# 40bus-nano32.net
KiCad netlist of a schematic drawn in EAGLE
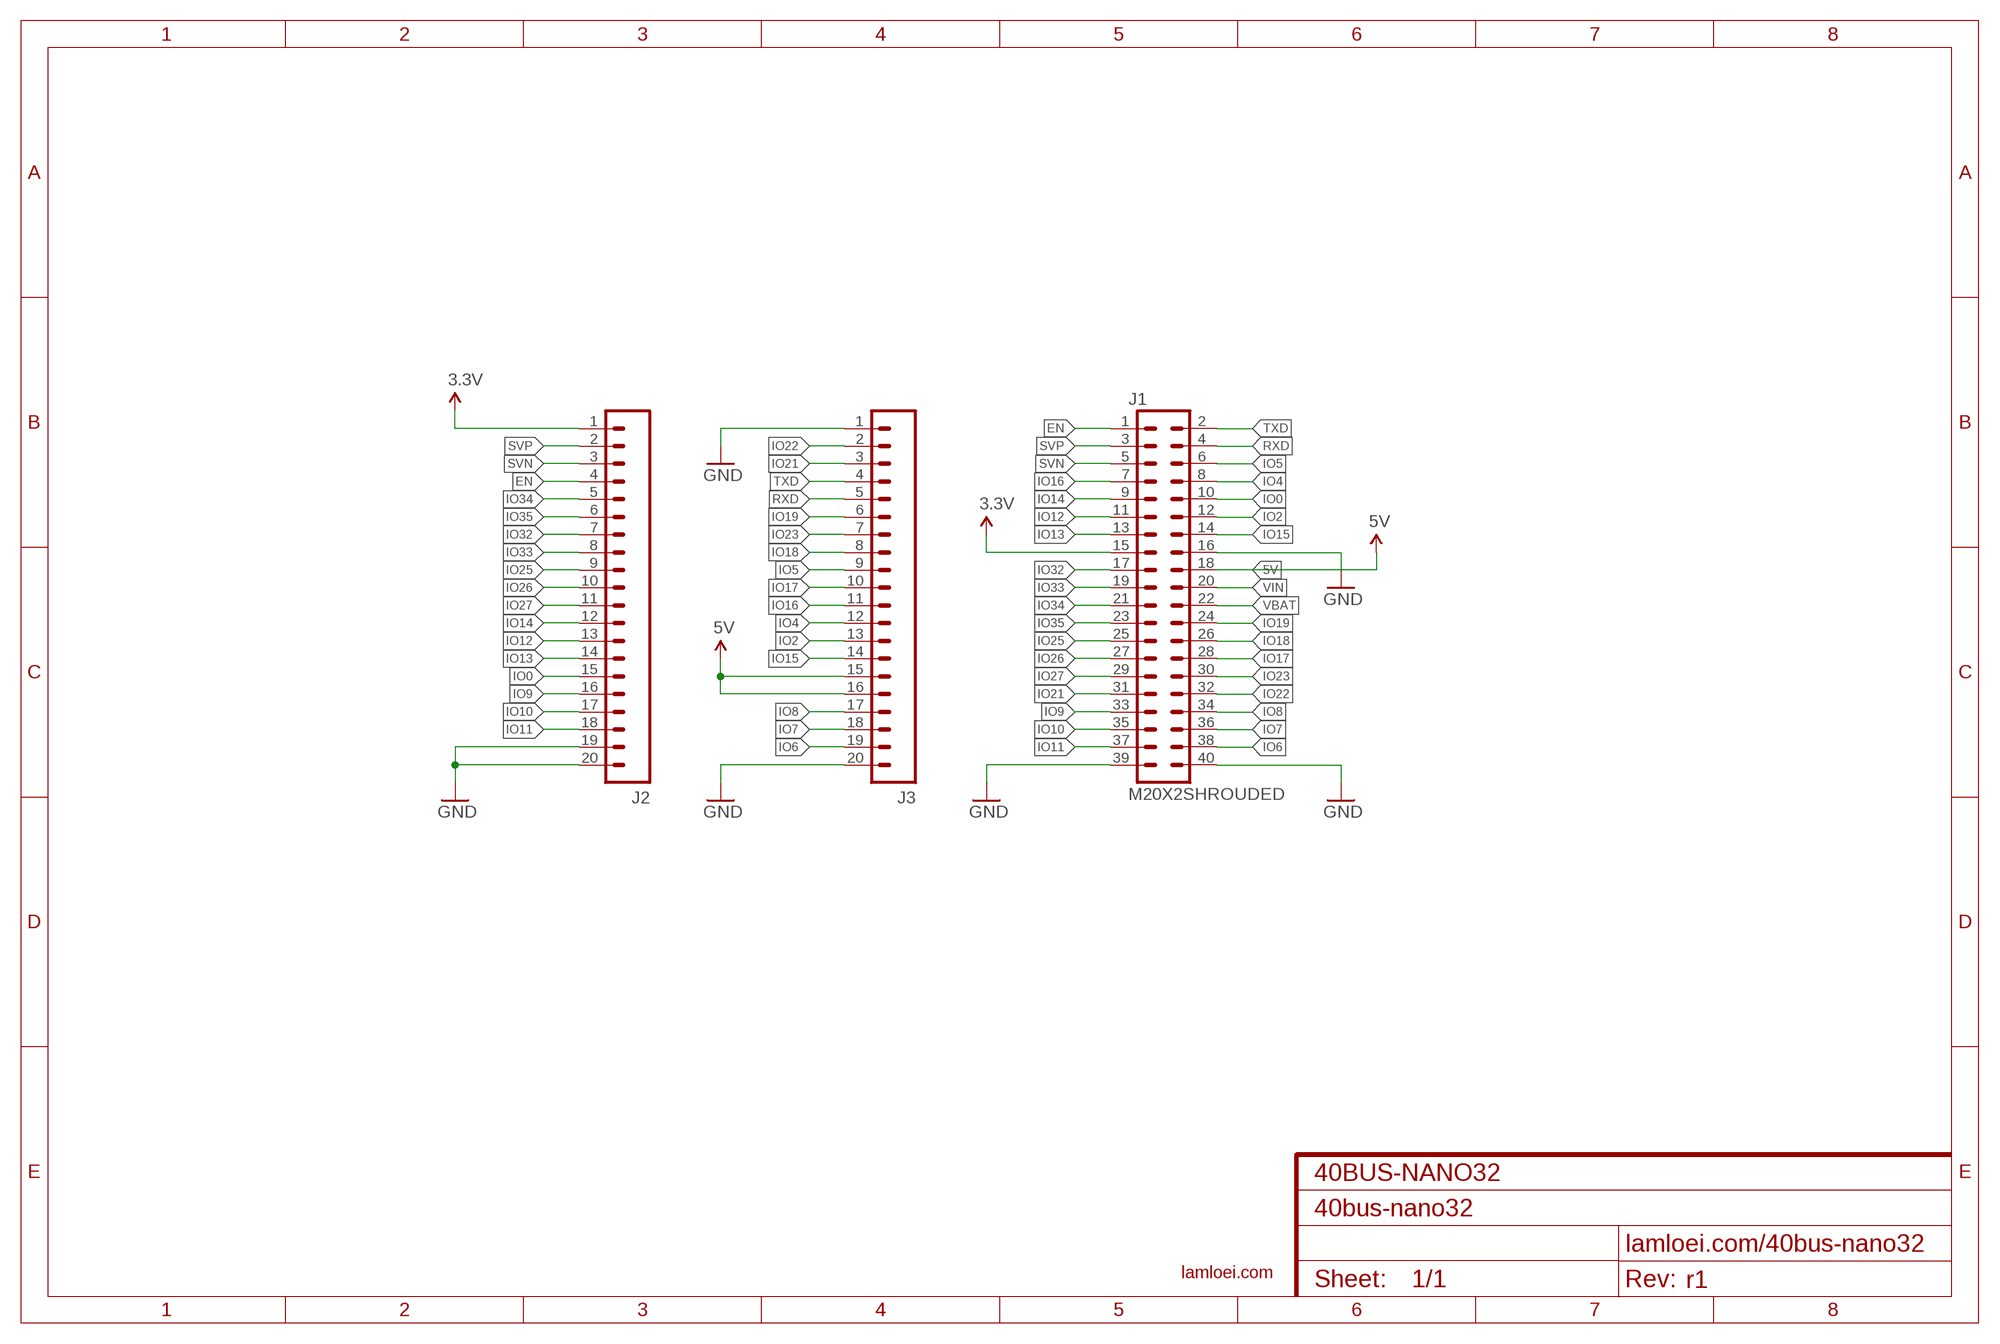
[diagram p0: schematic, sheet 1]

(export (version "E")
  (design (tool "Eeschema 10.0.6"))
  (components
    (comp (ref "J1")
      (value "M20X2SHROUDED")
      (footprint "eagle-import:2X20_SHROUDED")
      (libsource (lib "eagle-import") (part "M20X2SHROUDED"))
    )
    (comp (ref "J2")
      (value "M20")
      (footprint "eagle-import:1X20")
      (libsource (lib "eagle-import") (part "M20"))
    )
    (comp (ref "J3")
      (value "M20")
      (footprint "eagle-import:1X20")
      (libsource (lib "eagle-import") (part "M20"))
    )
    (comp (ref "U$1")
      (value "LAMLEOI_LOGO_3")
      (footprint "eagle-import:LAMLEOI_LOGO_3")
      (libsource (lib "eagle-import") (part "LAMLEOI_LOGO_3"))
    )
  )
  (nets
    (net (code "1") (name "3.3V") (class "Default")
      (node (ref "J1") (pin "15") (pinfunction "15_15") (pintype "passive"))
      (node (ref "J2") (pin "1") (pinfunction "1_1") (pintype "passive"))
    )
    (net (code "2") (name "5V") (class "Default")
      (node (ref "J1") (pin "18") (pinfunction "18_18") (pintype "passive"))
      (node (ref "J3") (pin "15") (pinfunction "15_15") (pintype "passive"))
      (node (ref "J3") (pin "16") (pinfunction "16_16") (pintype "passive"))
    )
    (net (code "3") (name "EN") (class "Default")
      (node (ref "J1") (pin "1") (pinfunction "1_1") (pintype "passive"))
      (node (ref "J2") (pin "4") (pinfunction "4_4") (pintype "passive"))
    )
    (net (code "4") (name "GND") (class "Default")
      (node (ref "J1") (pin "16") (pinfunction "16_16") (pintype "passive"))
      (node (ref "J1") (pin "39") (pinfunction "39_39") (pintype "passive"))
      (node (ref "J1") (pin "40") (pinfunction "40_40") (pintype "passive"))
      (node (ref "J2") (pin "19") (pinfunction "19_19") (pintype "passive"))
      (node (ref "J2") (pin "20") (pinfunction "20_20") (pintype "passive"))
      (node (ref "J3") (pin "1") (pinfunction "1_1") (pintype "passive"))
      (node (ref "J3") (pin "20") (pinfunction "20_20") (pintype "passive"))
    )
    (net (code "5") (name "IO0") (class "Default")
      (node (ref "J1") (pin "10") (pinfunction "10_10") (pintype "passive"))
      (node (ref "J2") (pin "15") (pinfunction "15_15") (pintype "passive"))
    )
    (net (code "6") (name "IO2") (class "Default")
      (node (ref "J1") (pin "12") (pinfunction "12_12") (pintype "passive"))
      (node (ref "J3") (pin "13") (pinfunction "13_13") (pintype "passive"))
    )
    (net (code "7") (name "IO4") (class "Default")
      (node (ref "J1") (pin "8") (pinfunction "8_8") (pintype "passive"))
      (node (ref "J3") (pin "12") (pinfunction "12_12") (pintype "passive"))
    )
    (net (code "8") (name "IO5") (class "Default")
      (node (ref "J1") (pin "6") (pinfunction "6_6") (pintype "passive"))
      (node (ref "J3") (pin "9") (pinfunction "9_9") (pintype "passive"))
    )
    (net (code "9") (name "IO6") (class "Default")
      (node (ref "J1") (pin "38") (pinfunction "38_38") (pintype "passive"))
      (node (ref "J3") (pin "19") (pinfunction "19_19") (pintype "passive"))
    )
    (net (code "10") (name "IO7") (class "Default")
      (node (ref "J1") (pin "36") (pinfunction "36_36") (pintype "passive"))
      (node (ref "J3") (pin "18") (pinfunction "18_18") (pintype "passive"))
    )
    (net (code "11") (name "IO8") (class "Default")
      (node (ref "J1") (pin "34") (pinfunction "34_34") (pintype "passive"))
      (node (ref "J3") (pin "17") (pinfunction "17_17") (pintype "passive"))
    )
    (net (code "12") (name "IO9") (class "Default")
      (node (ref "J1") (pin "33") (pinfunction "33_33") (pintype "passive"))
      (node (ref "J2") (pin "16") (pinfunction "16_16") (pintype "passive"))
    )
    (net (code "13") (name "IO10") (class "Default")
      (node (ref "J1") (pin "35") (pinfunction "35_35") (pintype "passive"))
      (node (ref "J2") (pin "17") (pinfunction "17_17") (pintype "passive"))
    )
    (net (code "14") (name "IO11") (class "Default")
      (node (ref "J1") (pin "37") (pinfunction "37_37") (pintype "passive"))
      (node (ref "J2") (pin "18") (pinfunction "18_18") (pintype "passive"))
    )
    (net (code "15") (name "IO12") (class "Default")
      (node (ref "J1") (pin "11") (pinfunction "11_11") (pintype "passive"))
      (node (ref "J2") (pin "13") (pinfunction "13_13") (pintype "passive"))
    )
    (net (code "16") (name "IO13") (class "Default")
      (node (ref "J1") (pin "13") (pinfunction "13_13") (pintype "passive"))
      (node (ref "J2") (pin "14") (pinfunction "14_14") (pintype "passive"))
    )
    (net (code "17") (name "IO14") (class "Default")
      (node (ref "J1") (pin "9") (pinfunction "9_9") (pintype "passive"))
      (node (ref "J2") (pin "12") (pinfunction "12_12") (pintype "passive"))
    )
    (net (code "18") (name "IO15") (class "Default")
      (node (ref "J1") (pin "14") (pinfunction "14_14") (pintype "passive"))
      (node (ref "J3") (pin "14") (pinfunction "14_14") (pintype "passive"))
    )
    (net (code "19") (name "IO16") (class "Default")
      (node (ref "J1") (pin "7") (pinfunction "7_7") (pintype "passive"))
      (node (ref "J3") (pin "11") (pinfunction "11_11") (pintype "passive"))
    )
    (net (code "20") (name "IO17") (class "Default")
      (node (ref "J1") (pin "28") (pinfunction "28_28") (pintype "passive"))
      (node (ref "J3") (pin "10") (pinfunction "10_10") (pintype "passive"))
    )
    (net (code "21") (name "IO18") (class "Default")
      (node (ref "J1") (pin "26") (pinfunction "26_26") (pintype "passive"))
      (node (ref "J3") (pin "8") (pinfunction "8_8") (pintype "passive"))
    )
    (net (code "22") (name "IO19") (class "Default")
      (node (ref "J1") (pin "24") (pinfunction "24_24") (pintype "passive"))
      (node (ref "J3") (pin "6") (pinfunction "6_6") (pintype "passive"))
    )
    (net (code "23") (name "IO21") (class "Default")
      (node (ref "J1") (pin "31") (pinfunction "31_31") (pintype "passive"))
      (node (ref "J3") (pin "3") (pinfunction "3_3") (pintype "passive"))
    )
    (net (code "24") (name "IO22") (class "Default")
      (node (ref "J1") (pin "32") (pinfunction "32_32") (pintype "passive"))
      (node (ref "J3") (pin "2") (pinfunction "2_2") (pintype "passive"))
    )
    (net (code "25") (name "IO23") (class "Default")
      (node (ref "J1") (pin "30") (pinfunction "30_30") (pintype "passive"))
      (node (ref "J3") (pin "7") (pinfunction "7_7") (pintype "passive"))
    )
    (net (code "26") (name "IO25") (class "Default")
      (node (ref "J1") (pin "25") (pinfunction "25_25") (pintype "passive"))
      (node (ref "J2") (pin "9") (pinfunction "9_9") (pintype "passive"))
    )
    (net (code "27") (name "IO26") (class "Default")
      (node (ref "J1") (pin "27") (pinfunction "27_27") (pintype "passive"))
      (node (ref "J2") (pin "10") (pinfunction "10_10") (pintype "passive"))
    )
    (net (code "28") (name "IO27") (class "Default")
      (node (ref "J1") (pin "29") (pinfunction "29_29") (pintype "passive"))
      (node (ref "J2") (pin "11") (pinfunction "11_11") (pintype "passive"))
    )
    (net (code "29") (name "IO32") (class "Default")
      (node (ref "J1") (pin "17") (pinfunction "17_17") (pintype "passive"))
      (node (ref "J2") (pin "7") (pinfunction "7_7") (pintype "passive"))
    )
    (net (code "30") (name "IO33") (class "Default")
      (node (ref "J1") (pin "19") (pinfunction "19_19") (pintype "passive"))
      (node (ref "J2") (pin "8") (pinfunction "8_8") (pintype "passive"))
    )
    (net (code "31") (name "IO34") (class "Default")
      (node (ref "J1") (pin "21") (pinfunction "21_21") (pintype "passive"))
      (node (ref "J2") (pin "5") (pinfunction "5_5") (pintype "passive"))
    )
    (net (code "32") (name "IO35") (class "Default")
      (node (ref "J1") (pin "23") (pinfunction "23_23") (pintype "passive"))
      (node (ref "J2") (pin "6") (pinfunction "6_6") (pintype "passive"))
    )
    (net (code "33") (name "RXD") (class "Default")
      (node (ref "J1") (pin "4") (pinfunction "4_4") (pintype "passive"))
      (node (ref "J3") (pin "5") (pinfunction "5_5") (pintype "passive"))
    )
    (net (code "34") (name "SVN") (class "Default")
      (node (ref "J1") (pin "5") (pinfunction "5_5") (pintype "passive"))
      (node (ref "J2") (pin "3") (pinfunction "3_3") (pintype "passive"))
    )
    (net (code "35") (name "SVP") (class "Default")
      (node (ref "J1") (pin "3") (pinfunction "3_3") (pintype "passive"))
      (node (ref "J2") (pin "2") (pinfunction "2_2") (pintype "passive"))
    )
    (net (code "36") (name "TXD") (class "Default")
      (node (ref "J1") (pin "2") (pinfunction "2_2") (pintype "passive"))
      (node (ref "J3") (pin "4") (pinfunction "4_4") (pintype "passive"))
    )
    (net (code "37") (name "VBAT") (class "Default")
      (node (ref "J1") (pin "22") (pinfunction "22_22") (pintype "passive"))
    )
    (net (code "38") (name "VIN") (class "Default")
      (node (ref "J1") (pin "20") (pinfunction "20_20") (pintype "passive"))
    )
  )
)
